# MySLipo_v2_0.net
KiCad netlist of a schematic drawn in EAGLE
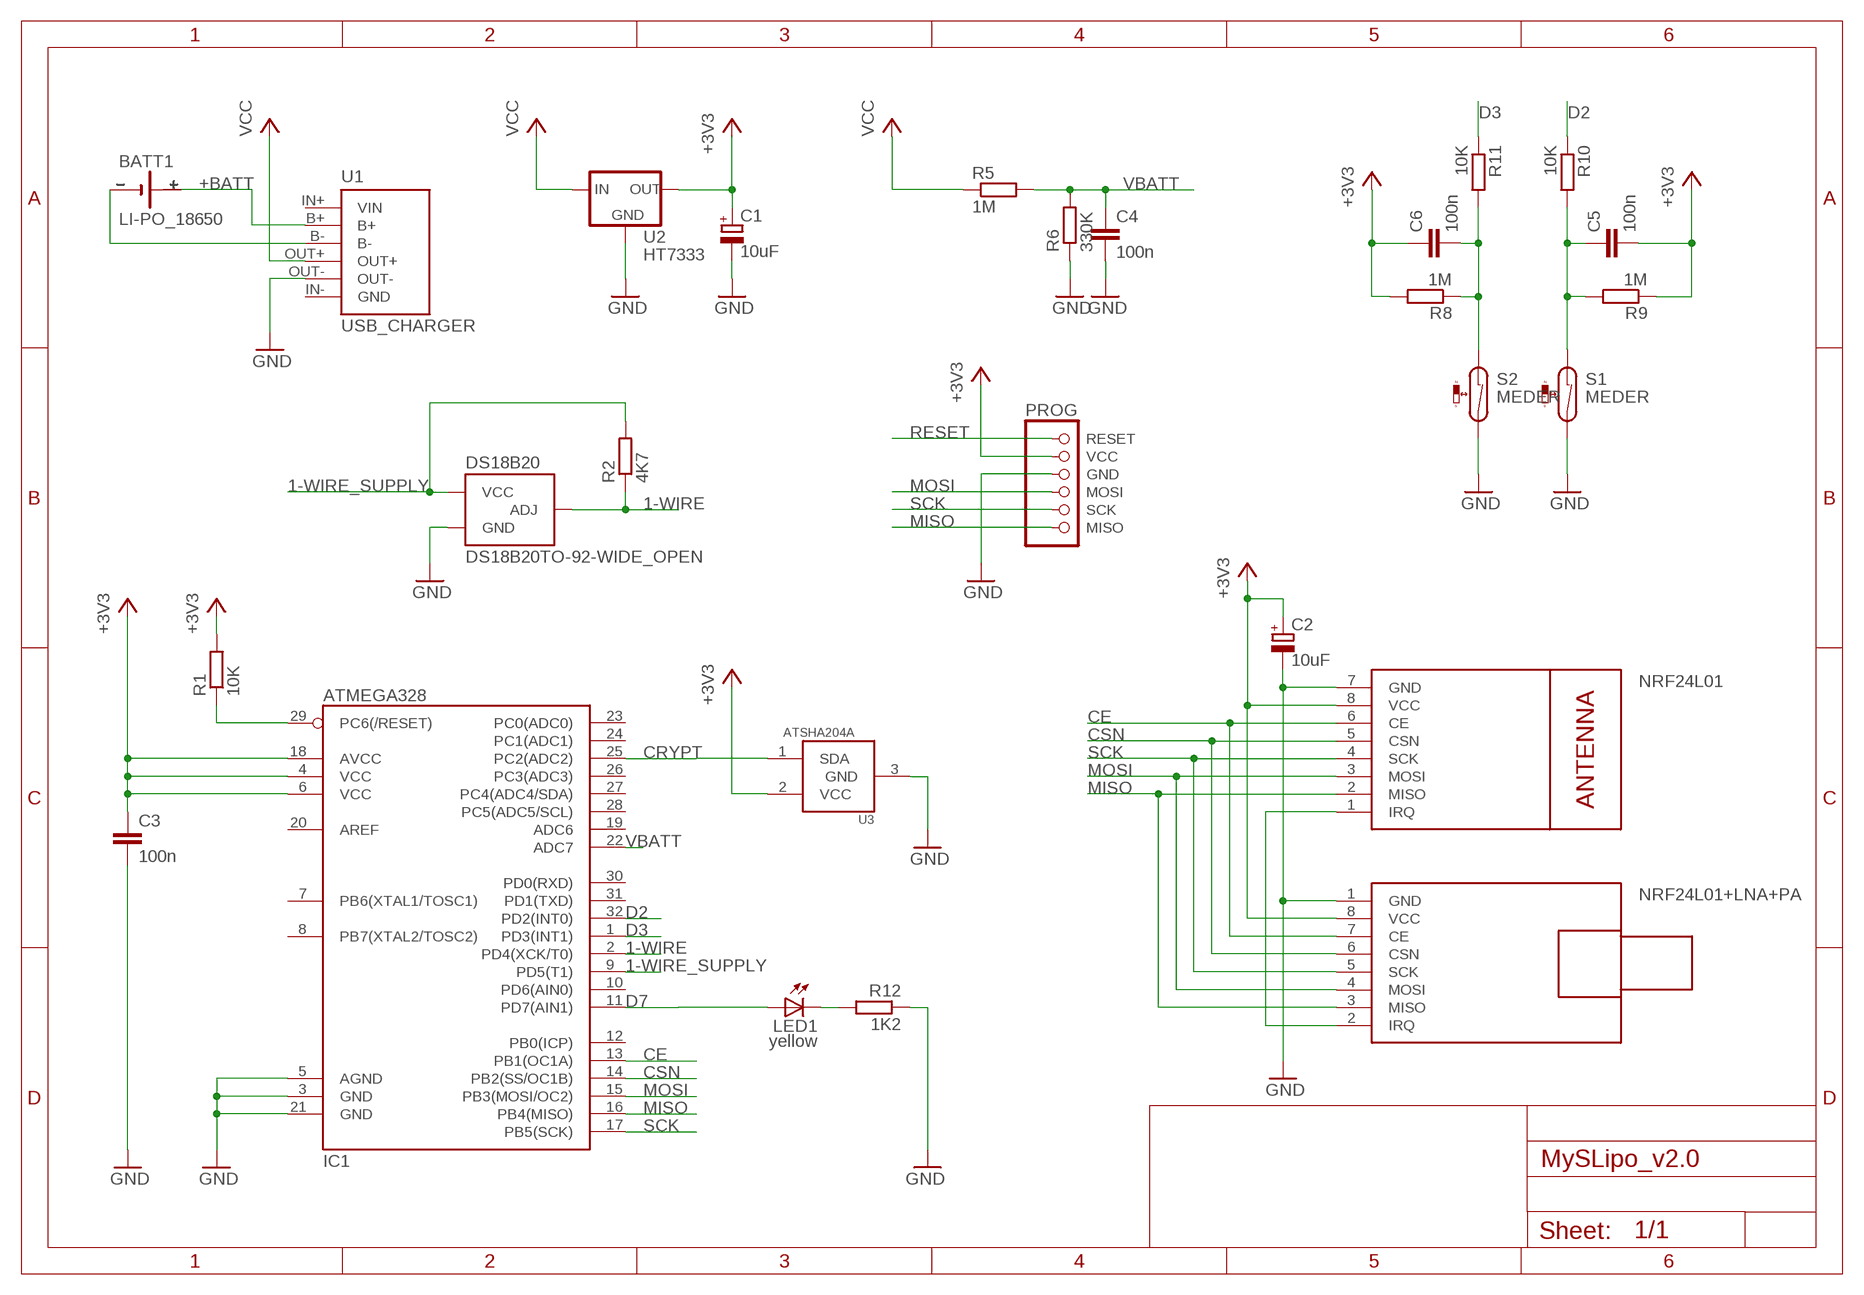
[diagram p0: schematic, sheet 1]

(export (version "E")
  (design (tool "Eeschema 10.0.6"))
  (components
    (comp (ref "BATT1")
      (value "LI-PO_18650")
      (footprint "eagle-import:18650_HOLDER")
      (libsource (lib "eagle-import") (part "SINGLE_BATTERY_HOLDER18650"))
    )
    (comp (ref "C1")
      (value "10uF")
      (footprint "eagle-import:SMC_A")
      (libsource (lib "eagle-import") (part "CPOL-EUSMCA"))
    )
    (comp (ref "C2")
      (value "10uF")
      (footprint "eagle-import:SMC_A")
      (libsource (lib "eagle-import") (part "CPOL-EUSMCA"))
    )
    (comp (ref "C3")
      (value "100n")
      (footprint "eagle-import:C0805")
      (libsource (lib "eagle-import") (part "C-EUC0805"))
    )
    (comp (ref "C4")
      (value "100n")
      (footprint "eagle-import:C0805")
      (libsource (lib "eagle-import") (part "C-EUC0805"))
    )
    (comp (ref "C5")
      (value "100n")
      (footprint "eagle-import:C0805")
      (libsource (lib "eagle-import") (part "C-EUC0805"))
    )
    (comp (ref "C6")
      (value "100n")
      (footprint "eagle-import:C0805")
      (libsource (lib "eagle-import") (part "C-EUC0805"))
    )
    (comp (ref "DS18B20")
      (value "DS18B20TO-92-WIDE_OPEN")
      (footprint "eagle-import:TO-92-WIDE_OPEN")
      (libsource (lib "eagle-import") (part "DS18B20TO-92-WIDE_OPEN"))
    )
    (comp (ref "IC1")
      (value "ATMEGA328")
      (footprint "eagle-import:TQFP32-08")
      (libsource (lib "eagle-import") (part "ATMEGA328"))
    )
    (comp (ref "LED1")
      (value "yellow")
      (footprint "eagle-import:LED_0805")
      (libsource (lib "eagle-import") (part "LED"))
    )
    (comp (ref "NRF24L01")
      (value "WIRELESS-NRF24L01SMD2")
      (footprint "eagle-import:WIRELESS-NRF24L01-SMD-2")
      (libsource (lib "eagle-import") (part "WIRELESS-NRF24L01SMD2"))
    )
    (comp (ref "NRF24L01+LNA+PA")
      (value "WIRELESS-NRF24L01-PA-EXTSMD")
      (footprint "eagle-import:WIRELESS-NRF24L01-PA-SMD")
      (libsource (lib "eagle-import") (part "WIRELESS-NRF24L01-PA-EXTSMD"))
    )
    (comp (ref "PROG")
      (value "PROG")
      (footprint "eagle-import:PROG")
      (libsource (lib "eagle-import") (part "PROG"))
    )
    (comp (ref "R1")
      (value "10K")
      (footprint "eagle-import:R0805")
      (libsource (lib "eagle-import") (part "R-EU_R0805"))
    )
    (comp (ref "R2")
      (value "4K7")
      (footprint "eagle-import:R0805")
      (libsource (lib "eagle-import") (part "R-EU_R0805"))
    )
    (comp (ref "R5")
      (value "1M")
      (footprint "eagle-import:R0805")
      (libsource (lib "eagle-import") (part "R-EU_R0805"))
    )
    (comp (ref "R6")
      (value "330K")
      (footprint "eagle-import:R0805")
      (libsource (lib "eagle-import") (part "R-EU_R0805"))
    )
    (comp (ref "R8")
      (value "1M")
      (footprint "eagle-import:R0805")
      (libsource (lib "eagle-import") (part "R-EU_R0805"))
    )
    (comp (ref "R9")
      (value "1M")
      (footprint "eagle-import:R0805")
      (libsource (lib "eagle-import") (part "R-EU_R0805"))
    )
    (comp (ref "R10")
      (value "10K")
      (footprint "eagle-import:R0805")
      (libsource (lib "eagle-import") (part "R-EU_R0805"))
    )
    (comp (ref "R11")
      (value "10K")
      (footprint "eagle-import:R0805")
      (libsource (lib "eagle-import") (part "R-EU_R0805"))
    )
    (comp (ref "R12")
      (value "1K2")
      (footprint "eagle-import:R0805")
      (libsource (lib "eagle-import") (part "R-EU_R0805"))
    )
    (comp (ref "S1")
      (value "MEDER")
      (footprint "eagle-import:15X")
      (libsource (lib "eagle-import") (part "MEDER"))
    )
    (comp (ref "S2")
      (value "MEDER")
      (footprint "eagle-import:15X")
      (libsource (lib "eagle-import") (part "MEDER"))
    )
    (comp (ref "U1")
      (value "USB_CHARGER")
      (footprint "eagle-import:USB_CHARGER")
      (libsource (lib "eagle-import") (part "USB_CHARGER"))
    )
    (comp (ref "U2")
      (value "HT7333")
      (footprint "eagle-import:SOT89")
      (libsource (lib "eagle-import") (part "HT7333"))
    )
    (comp (ref "U3")
      (value "ATSHA204A")
      (footprint "eagle-import:SOT23-3")
      (libsource (lib "eagle-import") (part "IC_ATSHA204A_CRYPT"))
    )
  )
  (nets
    (net (code "1") (name "+3V3") (class "Default")
      (node (ref "C1") (pin "+") (pinfunction "+_+") (pintype "passive"))
      (node (ref "C2") (pin "+") (pinfunction "+_+") (pintype "passive"))
      (node (ref "C3") (pin "1") (pinfunction "1_1") (pintype "passive"))
      (node (ref "C5") (pin "2") (pinfunction "2_2") (pintype "passive"))
      (node (ref "C6") (pin "1") (pinfunction "1_1") (pintype "passive"))
      (node (ref "IC1") (pin "18") (pinfunction "AVCC_18") (pintype "bidirectional"))
      (node (ref "IC1") (pin "4") (pinfunction "VCC_4") (pintype "bidirectional"))
      (node (ref "IC1") (pin "6") (pinfunction "VCC_6") (pintype "bidirectional"))
      (node (ref "NRF24L01") (pin "8") (pinfunction "VCC_8") (pintype "power_in"))
      (node (ref "NRF24L01+LNA+PA") (pin "8") (pinfunction "VCC_8") (pintype "power_in"))
      (node (ref "PROG") (pin "2") (pinfunction "VCC_2") (pintype "passive"))
      (node (ref "R1") (pin "2") (pinfunction "2_2") (pintype "passive"))
      (node (ref "R8") (pin "2") (pinfunction "2_2") (pintype "passive"))
      (node (ref "R9") (pin "1") (pinfunction "1_1") (pintype "passive"))
      (node (ref "U2") (pin "3") (pinfunction "OUT_3") (pintype "output"))
      (node (ref "U3") (pin "2") (pinfunction "VCC_2") (pintype "bidirectional"))
    )
    (net (code "2") (name "/+BATT") (class "Default")
      (node (ref "BATT1") (pin "+") (pinfunction "+_+") (pintype "passive"))
      (node (ref "U1") (pin "B+") (pinfunction "B+_B+") (pintype "bidirectional"))
    )
    (net (code "3") (name "/1-WIRE") (class "Default")
      (node (ref "DS18B20") (pin "G") (pinfunction "ADJ_G") (pintype "output"))
      (node (ref "IC1") (pin "2") (pinfunction "PD4(XCK/T0)_2") (pintype "bidirectional"))
      (node (ref "R2") (pin "1") (pinfunction "1_1") (pintype "passive"))
    )
    (net (code "4") (name "/1-WIRE_SUPPLY") (class "Default")
      (node (ref "DS18B20") (pin "S") (pinfunction "VCC_S") (pintype "passive"))
      (node (ref "IC1") (pin "9") (pinfunction "PD5(T1)_9") (pintype "bidirectional"))
      (node (ref "R2") (pin "2") (pinfunction "2_2") (pintype "passive"))
    )
    (net (code "5") (name "/CE") (class "Default")
      (node (ref "IC1") (pin "13") (pinfunction "PB1(OC1A)_13") (pintype "bidirectional"))
      (node (ref "NRF24L01") (pin "6") (pinfunction "CE_6") (pintype "bidirectional"))
      (node (ref "NRF24L01+LNA+PA") (pin "7") (pinfunction "CE_7") (pintype "bidirectional"))
    )
    (net (code "6") (name "/CRYPT") (class "Default")
      (node (ref "IC1") (pin "25") (pinfunction "PC2(ADC2)_25") (pintype "bidirectional"))
      (node (ref "U3") (pin "1") (pinfunction "SDA_1") (pintype "bidirectional"))
    )
    (net (code "7") (name "/CSN") (class "Default")
      (node (ref "IC1") (pin "14") (pinfunction "PB2(SS/OC1B)_14") (pintype "bidirectional"))
      (node (ref "NRF24L01") (pin "5") (pinfunction "CSN_5") (pintype "bidirectional"))
      (node (ref "NRF24L01+LNA+PA") (pin "6") (pinfunction "CSN_6") (pintype "bidirectional"))
    )
    (net (code "8") (name "/D2") (class "Default")
      (node (ref "IC1") (pin "32") (pinfunction "PD2(INT0)_32") (pintype "bidirectional"))
      (node (ref "R10") (pin "1") (pinfunction "1_1") (pintype "passive"))
    )
    (net (code "9") (name "/D3") (class "Default")
      (node (ref "IC1") (pin "1") (pinfunction "PD3(INT1)_1") (pintype "bidirectional"))
      (node (ref "R11") (pin "1") (pinfunction "1_1") (pintype "passive"))
    )
    (net (code "10") (name "/D7") (class "Default")
      (node (ref "IC1") (pin "11") (pinfunction "PD7(AIN1)_11") (pintype "bidirectional"))
      (node (ref "LED1") (pin "1") (pinfunction "A_1") (pintype "passive"))
    )
    (net (code "11") (name "/MISO") (class "Default")
      (node (ref "IC1") (pin "16") (pinfunction "PB4(MISO)_16") (pintype "bidirectional"))
      (node (ref "NRF24L01") (pin "2") (pinfunction "MISO_2") (pintype "bidirectional"))
      (node (ref "NRF24L01+LNA+PA") (pin "3") (pinfunction "MISO_3") (pintype "bidirectional"))
      (node (ref "PROG") (pin "6") (pinfunction "MISO_6") (pintype "passive"))
    )
    (net (code "12") (name "/MOSI") (class "Default")
      (node (ref "IC1") (pin "15") (pinfunction "PB3(MOSI/OC2)_15") (pintype "bidirectional"))
      (node (ref "NRF24L01") (pin "3") (pinfunction "MOSI_3") (pintype "bidirectional"))
      (node (ref "NRF24L01+LNA+PA") (pin "4") (pinfunction "MOSI_4") (pintype "bidirectional"))
      (node (ref "PROG") (pin "4") (pinfunction "MOSI_4") (pintype "passive"))
    )
    (net (code "13") (name "/RESET") (class "Default")
      (node (ref "IC1") (pin "29") (pinfunction "PC6(/RESET)_29") (pintype "bidirectional"))
      (node (ref "PROG") (pin "1") (pinfunction "RESET_1") (pintype "passive"))
      (node (ref "R1") (pin "1") (pinfunction "1_1") (pintype "passive"))
    )
    (net (code "14") (name "/SCK") (class "Default")
      (node (ref "IC1") (pin "17") (pinfunction "PB5(SCK)_17") (pintype "bidirectional"))
      (node (ref "NRF24L01") (pin "4") (pinfunction "SCK_4") (pintype "bidirectional"))
      (node (ref "NRF24L01+LNA+PA") (pin "5") (pinfunction "SCK_5") (pintype "bidirectional"))
      (node (ref "PROG") (pin "5") (pinfunction "SCK_5") (pintype "passive"))
    )
    (net (code "15") (name "/VBATT") (class "Default")
      (node (ref "C4") (pin "1") (pinfunction "1_1") (pintype "passive"))
      (node (ref "IC1") (pin "22") (pinfunction "ADC7_22") (pintype "bidirectional"))
      (node (ref "R5") (pin "2") (pinfunction "2_2") (pintype "passive"))
      (node (ref "R6") (pin "2") (pinfunction "2_2") (pintype "passive"))
    )
    (net (code "16") (name "GND") (class "Default")
      (node (ref "C1") (pin "-") (pinfunction "-_-") (pintype "passive"))
      (node (ref "C2") (pin "-") (pinfunction "-_-") (pintype "passive"))
      (node (ref "C3") (pin "2") (pinfunction "2_2") (pintype "passive"))
      (node (ref "C4") (pin "2") (pinfunction "2_2") (pintype "passive"))
      (node (ref "DS18B20") (pin "D") (pinfunction "GND_D") (pintype "power_in"))
      (node (ref "IC1") (pin "21") (pinfunction "GND_21") (pintype "bidirectional"))
      (node (ref "IC1") (pin "3") (pinfunction "GND_3") (pintype "bidirectional"))
      (node (ref "IC1") (pin "5") (pinfunction "AGND_5") (pintype "bidirectional"))
      (node (ref "NRF24L01") (pin "7") (pinfunction "GND_7") (pintype "power_in"))
      (node (ref "NRF24L01+LNA+PA") (pin "1") (pinfunction "GND_1") (pintype "power_in"))
      (node (ref "PROG") (pin "3") (pinfunction "GND_3") (pintype "passive"))
      (node (ref "R12") (pin "1") (pinfunction "1_1") (pintype "passive"))
      (node (ref "R6") (pin "1") (pinfunction "1_1") (pintype "passive"))
      (node (ref "S1") (pin "P$2") (pinfunction "2_P$2") (pintype "passive"))
      (node (ref "S2") (pin "P$2") (pinfunction "2_P$2") (pintype "passive"))
      (node (ref "U1") (pin "OUT-") (pinfunction "OUT-_OUT-") (pintype "bidirectional"))
      (node (ref "U2") (pin "1") (pinfunction "GND_1") (pintype "input"))
      (node (ref "U3") (pin "3") (pinfunction "GND_3") (pintype "bidirectional"))
    )
    (net (code "17") (name "Net-(BATT1-Pad-)") (class "Default")
      (node (ref "BATT1") (pin "-") (pinfunction "-_-") (pintype "passive"))
      (node (ref "U1") (pin "B-") (pinfunction "B-_B-") (pintype "bidirectional"))
    )
    (net (code "18") (name "Net-(LED1-C)") (class "Default")
      (node (ref "LED1") (pin "2") (pinfunction "C_2") (pintype "passive"))
      (node (ref "R12") (pin "2") (pinfunction "2_2") (pintype "passive"))
    )
    (net (code "19") (name "Net-(NRF24L01+LNA+PA-IRQ)") (class "Default")
      (node (ref "NRF24L01") (pin "1") (pinfunction "IRQ_1") (pintype "bidirectional"))
      (node (ref "NRF24L01+LNA+PA") (pin "2") (pinfunction "IRQ_2") (pintype "bidirectional"))
    )
    (net (code "20") (name "Net-(S1-1)") (class "Default")
      (node (ref "C5") (pin "1") (pinfunction "1_1") (pintype "passive"))
      (node (ref "R10") (pin "2") (pinfunction "2_2") (pintype "passive"))
      (node (ref "R9") (pin "2") (pinfunction "2_2") (pintype "passive"))
      (node (ref "S1") (pin "P$1") (pinfunction "1_P$1") (pintype "passive"))
    )
    (net (code "21") (name "Net-(S2-1)") (class "Default")
      (node (ref "C6") (pin "2") (pinfunction "2_2") (pintype "passive"))
      (node (ref "R11") (pin "2") (pinfunction "2_2") (pintype "passive"))
      (node (ref "R8") (pin "1") (pinfunction "1_1") (pintype "passive"))
      (node (ref "S2") (pin "P$1") (pinfunction "1_P$1") (pintype "passive"))
    )
    (net (code "22") (name "VCC") (class "Default")
      (node (ref "R5") (pin "1") (pinfunction "1_1") (pintype "passive"))
      (node (ref "U1") (pin "OUT+") (pinfunction "OUT+_OUT+") (pintype "bidirectional"))
      (node (ref "U2") (pin "2") (pinfunction "IN_2") (pintype "input"))
    )
    (net (code "23") (name "unconnected-(IC1-ADC6-Pad19)") (class "Default")
      (node (ref "IC1") (pin "19") (pinfunction "ADC6_19") (pintype "bidirectional"))
    )
    (net (code "24") (name "unconnected-(IC1-AREF-Pad20)") (class "Default")
      (node (ref "IC1") (pin "20") (pinfunction "AREF_20") (pintype "bidirectional"))
    )
    (net (code "25") (name "unconnected-(IC1-PB0(ICP)-Pad12)") (class "Default")
      (node (ref "IC1") (pin "12") (pinfunction "PB0(ICP)_12") (pintype "bidirectional"))
    )
    (net (code "26") (name "unconnected-(IC1-PB6(XTAL1{slash}TOSC1)-Pad7)") (class "Default")
      (node (ref "IC1") (pin "7") (pinfunction "PB6(XTAL1/TOSC1)_7") (pintype "bidirectional"))
    )
    (net (code "27") (name "unconnected-(IC1-PB7(XTAL2{slash}TOSC2)-Pad8)") (class "Default")
      (node (ref "IC1") (pin "8") (pinfunction "PB7(XTAL2/TOSC2)_8") (pintype "bidirectional"))
    )
    (net (code "28") (name "unconnected-(IC1-PC0(ADC0)-Pad23)") (class "Default")
      (node (ref "IC1") (pin "23") (pinfunction "PC0(ADC0)_23") (pintype "bidirectional"))
    )
    (net (code "29") (name "unconnected-(IC1-PC1(ADC1)-Pad24)") (class "Default")
      (node (ref "IC1") (pin "24") (pinfunction "PC1(ADC1)_24") (pintype "bidirectional"))
    )
    (net (code "30") (name "unconnected-(IC1-PC3(ADC3)-Pad26)") (class "Default")
      (node (ref "IC1") (pin "26") (pinfunction "PC3(ADC3)_26") (pintype "bidirectional"))
    )
    (net (code "31") (name "unconnected-(IC1-PC4(ADC4{slash}SDA)-Pad27)") (class "Default")
      (node (ref "IC1") (pin "27") (pinfunction "PC4(ADC4/SDA)_27") (pintype "bidirectional"))
    )
    (net (code "32") (name "unconnected-(IC1-PC5(ADC5{slash}SCL)-Pad28)") (class "Default")
      (node (ref "IC1") (pin "28") (pinfunction "PC5(ADC5/SCL)_28") (pintype "bidirectional"))
    )
    (net (code "33") (name "unconnected-(IC1-PD0(RXD)-Pad30)") (class "Default")
      (node (ref "IC1") (pin "30") (pinfunction "PD0(RXD)_30") (pintype "bidirectional"))
    )
    (net (code "34") (name "unconnected-(IC1-PD1(TXD)-Pad31)") (class "Default")
      (node (ref "IC1") (pin "31") (pinfunction "PD1(TXD)_31") (pintype "bidirectional"))
    )
    (net (code "35") (name "unconnected-(IC1-PD6(AIN0)-Pad10)") (class "Default")
      (node (ref "IC1") (pin "10") (pinfunction "PD6(AIN0)_10") (pintype "bidirectional"))
    )
    (net (code "36") (name "unconnected-(U1-GND-PadIN-)") (class "Default")
      (node (ref "U1") (pin "IN-") (pinfunction "GND_IN-") (pintype "bidirectional"))
    )
    (net (code "37") (name "unconnected-(U1-VIN-PadIN+)") (class "Default")
      (node (ref "U1") (pin "IN+") (pinfunction "VIN_IN+") (pintype "bidirectional"))
    )
  )
)
